# SCH_Lanchester-Mower_2024-05-06_1.net
KiCad netlist of a schematic drawn in EasyEDA
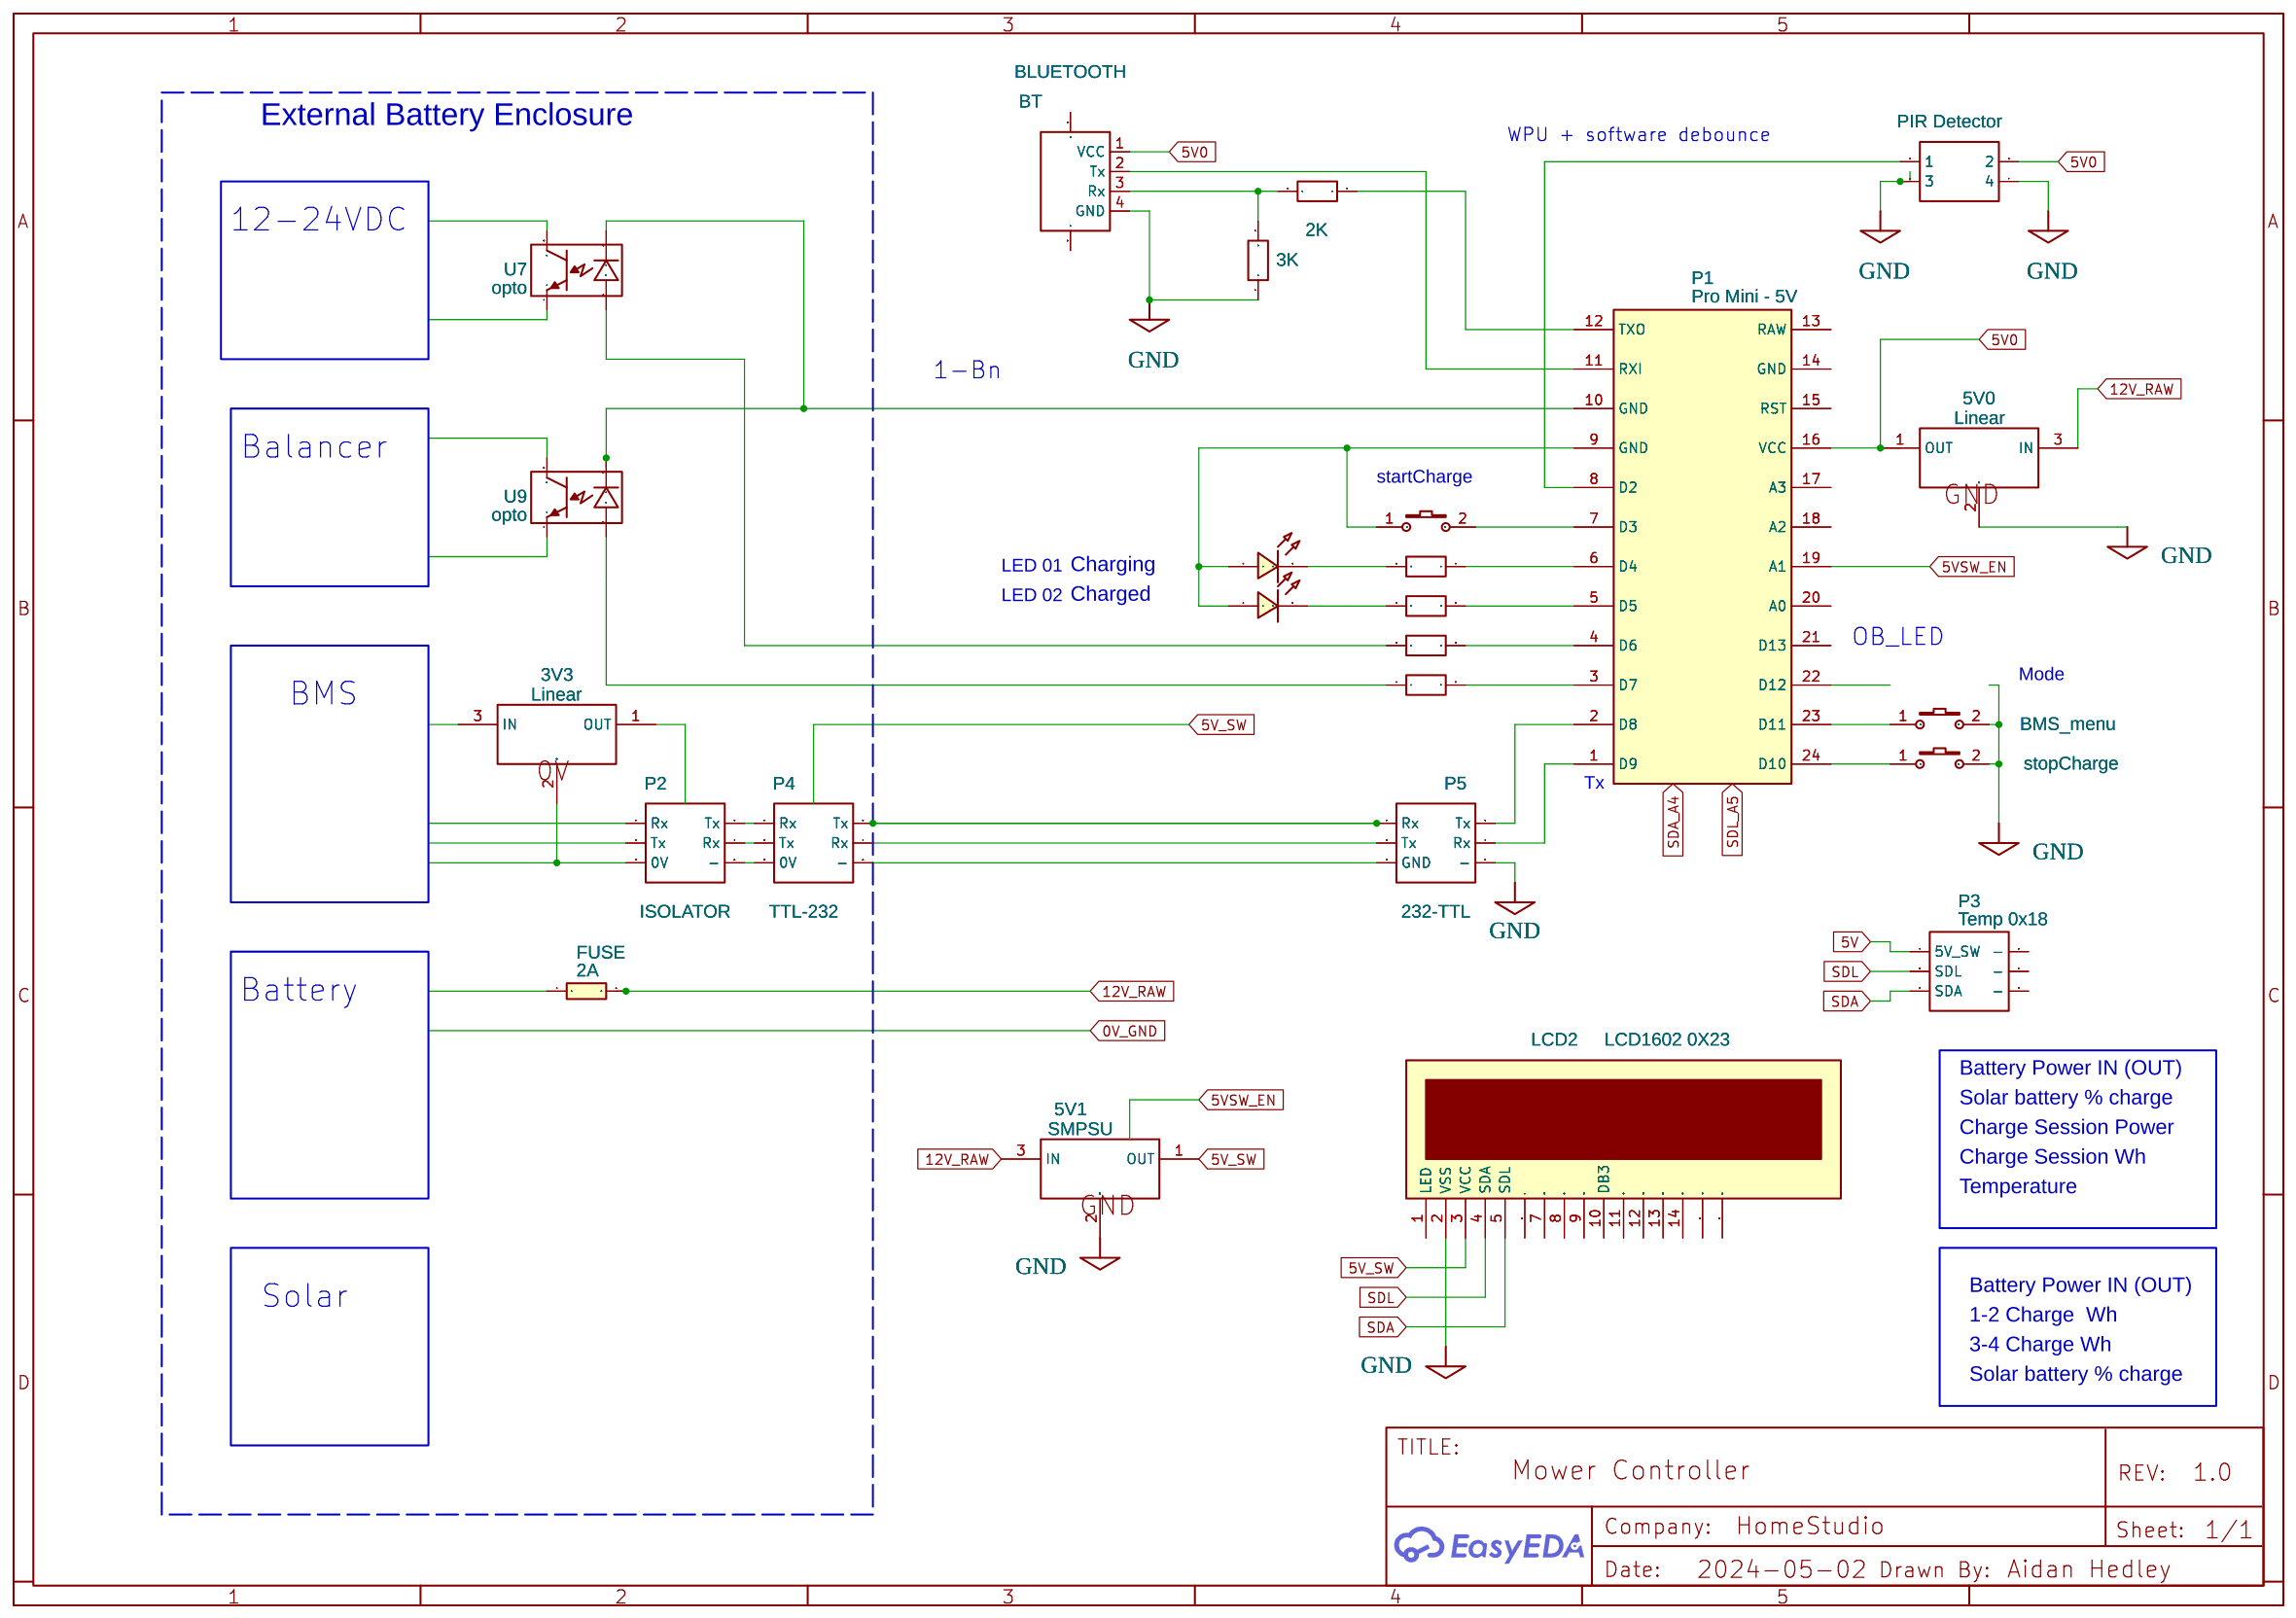
[diagram p0: schematic sheet]

(export (version "E")
  (design (tool "Eeschema 10.0.6"))
  (components
    (comp (ref "1R")
      (value "2K")
      (fields (field (name "Manufacturer Part") "贴片电阻ChipResistors"))
      (libsource (lib "") (part "贴片电阻CHIPRESISTORS_5"))
    )
    (comp (ref "3V3")
      (value "Linear")
      (fields (field (name "Manufacturer Part") "CJ78L05") (field (name "Manufacturer") "CJ"))
      (libsource (lib "") (part "7805(SOT-89)_2"))
    )
    (comp (ref "4R")
      (value "3K")
      (fields (field (name "Manufacturer Part") "贴片电阻ChipResistors"))
      (libsource (lib "") (part "贴片电阻CHIPRESISTORS_1"))
    )
    (comp (ref "5R")
      (value "R2")
      (fields (field (name "Manufacturer Part") "贴片电阻ChipResistors"))
      (libsource (lib "") (part "贴片电阻CHIPRESISTORS_4"))
    )
    (comp (ref "5V0")
      (value "Linear")
      (fields (field (name "Manufacturer Part") "CJ78L05") (field (name "Manufacturer") "CJ"))
      (libsource (lib "") (part "7805(SOT-89)_1"))
    )
    (comp (ref "5V1")
      (value "SMPSU")
      (fields (field (name "Manufacturer Part") "CJ78L05") (field (name "Manufacturer") "CJ"))
      (libsource (lib "") (part "7805(SOT-89)"))
    )
    (comp (ref "12R")
      (value "R2")
      (fields (field (name "Manufacturer Part") "贴片电阻ChipResistors"))
      (libsource (lib "") (part "贴片电阻CHIPRESISTORS_2"))
    )
    (comp (ref "14R")
      (value "R2")
      (fields (field (name "Manufacturer Part") "贴片电阻ChipResistors"))
      (libsource (lib "") (part "贴片电阻CHIPRESISTORS"))
    )
    (comp (ref "15R")
      (value "R2")
      (fields (field (name "Manufacturer Part") "贴片电阻ChipResistors"))
      (libsource (lib "") (part "贴片电阻CHIPRESISTORS_3"))
    )
    (comp (ref "BLUETOOTH")
      (value "BT")
      (fields (field (name "Manufacturer Part") "USB-05") (field (name "Manufacturer") "SOFNG"))
      (libsource (lib "") (part "USB-Type A_Male"))
    )
    (comp (ref "FUSE") (value "2A") (libsource (lib "") (part "L0603_EU")))
    (comp (ref "J2") (value "PIR Detector") (libsource (lib "") (part "HDR-M-2.54_2x2")))
    (comp (ref "KEY1")
      (value "stopCharge")
      (fields (field (name "Manufacturer Part") "K2-1107ST-A4SW-06"))
      (libsource (lib "") (part "K2-3.6×6.1_SMD"))
    )
    (comp (ref "KEY3")
      (value "BMS_menu")
      (fields (field (name "Manufacturer Part") "K2-1107ST-A4SW-06"))
      (libsource (lib "") (part "K2-3.6×6.1_SMD"))
    )
    (comp (ref "KEY4")
      (value "Start_Charge")
      (fields (field (name "Manufacturer Part") "K2-1107ST-A4SW-06"))
      (libsource (lib "") (part "K2-3.6×6.1_SMD"))
    )
    (comp (ref "LCD2")
      (value "LCD1602 0X23")
      (fields
        (field (name "Manufacturer Part") "LCM1602K-NSW-BBW")
        (field (name "Manufacturer") "LONTECH(厦门龙特)")
      )
      (libsource (lib "") (part "LCD1602"))
    )
    (comp (ref "LED1")
      (value "LED-0603_R")
      (fields
        (field (name "Manufacturer Part") "19-217/R6C-AL1M2VY/3T")
        (field (name "Manufacturer") "EVERLIGHT(台湾亿光)")
      )
      (libsource (lib "") (part "LED-0603_R"))
    )
    (comp (ref "LED3")
      (value "LED-0603_R")
      (fields
        (field (name "Manufacturer Part") "19-217/R6C-AL1M2VY/3T")
        (field (name "Manufacturer") "EVERLIGHT(台湾亿光)")
      )
      (libsource (lib "") (part "LED-0603_R"))
    )
    (comp (ref "P1") (value "Pro Mini - 5V") (libsource (lib "") (part "Pro Micro - 5V - large")))
    (comp (ref "P2")
      (value "ISOLATOR")
      (fields (field (name "Manufacturer Part") "2X3 2.54mm IDC Box") (field (name "Manufacturer") "BOOMELE"))
      (libsource (lib "") (part "HDR-IDC-2.54-2X3P_1"))
    )
    (comp (ref "P3")
      (value "Temp 0x18")
      (fields (field (name "Manufacturer Part") "2X3 2.54mm IDC Box") (field (name "Manufacturer") "BOOMELE"))
      (libsource (lib "") (part "HDR-IDC-2.54-2X3P"))
    )
    (comp (ref "P4")
      (value "TTL-232")
      (fields (field (name "Manufacturer Part") "2X3 2.54mm IDC Box") (field (name "Manufacturer") "BOOMELE"))
      (libsource (lib "") (part "HDR-IDC-2.54-2X3P_1"))
    )
    (comp (ref "P5")
      (value "232-TTL")
      (fields (field (name "Manufacturer Part") "2X3 2.54mm IDC Box") (field (name "Manufacturer") "BOOMELE"))
      (libsource (lib "") (part "HDR-IDC-2.54-2X3P_2"))
    )
    (comp (ref "U7")
      (value "opto")
      (fields (field (name "Manufacturer Part") "OPB841L55") (field (name "Manufacturer") "OPTEK"))
      (libsource (lib "") (part "OPB841L55"))
    )
    (comp (ref "U9")
      (value "opto")
      (fields (field (name "Manufacturer Part") "OPB841L55") (field (name "Manufacturer") "OPTEK"))
      (libsource (lib "") (part "OPB841L55"))
    )
  )
  (nets
    (net (code "2") (name "5V") (class "Default")
      (node (ref "P3") (pin "1") (pinfunction "5V_SW_1") (pintype "unspecified"))
    )
    (net (code "3") (name "5V0") (class "Default")
      (node (ref "5V0") (pin "1") (pinfunction "OUT_1") (pintype "passive"))
      (node (ref "BLUETOOTH") (pin "1") (pinfunction "VCC_1") (pintype "input"))
      (node (ref "J2") (pin "2") (pinfunction "2_2") (pintype "input"))
      (node (ref "P1") (pin "16") (pinfunction "VCC_16") (pintype "unspecified"))
    )
    (net (code "4") (name "5VSW_EN") (class "Default")
      (node (ref "P1") (pin "19") (pinfunction "A1_19") (pintype "unspecified"))
    )
    (net (code "5") (name "5V_SW") (class "Default")
      (node (ref "5V1") (pin "1") (pinfunction "OUT_1") (pintype "passive"))
      (node (ref "LCD2") (pin "3") (pinfunction "VCC_3") (pintype "unspecified"))
    )
    (net (code "6") (name "12V_RAW") (class "Default")
      (node (ref "5V0") (pin "3") (pinfunction "IN_3") (pintype "passive"))
      (node (ref "5V1") (pin "3") (pinfunction "IN_3") (pintype "passive"))
      (node (ref "FUSE") (pin "2") (pinfunction "2_2") (pintype "unspecified"))
    )
    (net (code "7") (name "GND") (class "Default")
      (node (ref "4R") (pin "1") (pinfunction "1_1") (pintype "unspecified"))
      (node (ref "5V0") (pin "2") (pinfunction "GND_2") (pintype "passive"))
      (node (ref "5V1") (pin "2") (pinfunction "GND_2") (pintype "passive"))
      (node (ref "BLUETOOTH") (pin "4") (pinfunction "GND_4") (pintype "input"))
      (node (ref "J2") (pin "3") (pinfunction "3_3") (pintype "input"))
      (node (ref "J2") (pin "4") (pinfunction "4_4") (pintype "input"))
      (node (ref "KEY1") (pin "2") (pinfunction "2_2") (pintype "unspecified"))
      (node (ref "KEY3") (pin "2") (pinfunction "2_2") (pintype "unspecified"))
      (node (ref "LCD2") (pin "2") (pinfunction "VSS_2") (pintype "unspecified"))
      (node (ref "P5") (pin "6") (pinfunction "-_6") (pintype "unspecified"))
    )
    (net (code "8") (name "Net-(3V3-GND)") (class "Default")
      (node (ref "3V3") (pin "2") (pinfunction "GND_2") (pintype "passive"))
      (node (ref "P2") (pin "5") (pinfunction "0V_5") (pintype "unspecified"))
    )
    (net (code "9") (name "Net-(5R-Pad2)") (class "Default")
      (node (ref "5R") (pin "2") (pinfunction "2_2") (pintype "unspecified"))
      (node (ref "LED3") (pin "2") (pinfunction "2_2") (pintype "unspecified"))
    )
    (net (code "10") (name "Net-(12R-Pad1)") (class "Default")
      (node (ref "12R") (pin "1") (pinfunction "1_1") (pintype "unspecified"))
      (node (ref "LED1") (pin "2") (pinfunction "2_2") (pintype "unspecified"))
    )
    (net (code "11") (name "Net-(14R-Pad1)") (class "Default")
      (node (ref "14R") (pin "1") (pinfunction "1_1") (pintype "unspecified"))
      (node (ref "U7") (pin "2") (pinfunction "2_2") (pintype "unspecified"))
    )
    (net (code "12") (name "Net-(15R-Pad1)") (class "Default")
      (node (ref "15R") (pin "1") (pinfunction "1_1") (pintype "unspecified"))
      (node (ref "U9") (pin "2") (pinfunction "2_2") (pintype "unspecified"))
    )
    (net (code "13") (name "Net-(BLUETOOTH-Rx)") (class "Default")
      (node (ref "1R") (pin "2") (pinfunction "2_2") (pintype "unspecified"))
      (node (ref "4R") (pin "2") (pinfunction "2_2") (pintype "unspecified"))
      (node (ref "BLUETOOTH") (pin "3") (pinfunction "Rx_3") (pintype "input"))
    )
    (net (code "14") (name "Net-(BLUETOOTH-Tx)") (class "Default")
      (node (ref "BLUETOOTH") (pin "2") (pinfunction "Tx_2") (pintype "input"))
      (node (ref "P1") (pin "11") (pinfunction "RXI_11") (pintype "unspecified"))
    )
    (net (code "15") (name "Net-(KEY4-Pad1)") (class "Default")
      (node (ref "KEY4") (pin "1") (pinfunction "1_1") (pintype "unspecified"))
      (node (ref "LED1") (pin "1") (pinfunction "1_1") (pintype "unspecified"))
      (node (ref "LED3") (pin "1") (pinfunction "1_1") (pintype "unspecified"))
      (node (ref "P1") (pin "9") (pinfunction "GND_9") (pintype "unspecified"))
    )
    (net (code "16") (name "Net-(P1-D2)") (class "Default")
      (node (ref "J2") (pin "1") (pinfunction "1_1") (pintype "input"))
      (node (ref "P1") (pin "8") (pinfunction "D2_8") (pintype "unspecified"))
    )
    (net (code "17") (name "Net-(P1-D3)") (class "Default")
      (node (ref "KEY4") (pin "2") (pinfunction "2_2") (pintype "unspecified"))
      (node (ref "P1") (pin "7") (pinfunction "D3_7") (pintype "unspecified"))
    )
    (net (code "18") (name "Net-(P1-D4)") (class "Default")
      (node (ref "5R") (pin "1") (pinfunction "1_1") (pintype "unspecified"))
      (node (ref "P1") (pin "6") (pinfunction "D4_6") (pintype "unspecified"))
    )
    (net (code "19") (name "Net-(P1-D5)") (class "Default")
      (node (ref "12R") (pin "2") (pinfunction "2_2") (pintype "unspecified"))
      (node (ref "P1") (pin "5") (pinfunction "D5_5") (pintype "unspecified"))
    )
    (net (code "20") (name "Net-(P1-D6)") (class "Default")
      (node (ref "14R") (pin "2") (pinfunction "2_2") (pintype "unspecified"))
      (node (ref "P1") (pin "4") (pinfunction "D6_4") (pintype "unspecified"))
    )
    (net (code "21") (name "Net-(P1-D7)") (class "Default")
      (node (ref "15R") (pin "2") (pinfunction "2_2") (pintype "unspecified"))
      (node (ref "P1") (pin "3") (pinfunction "D7_3") (pintype "unspecified"))
    )
    (net (code "22") (name "Net-(P1-D8)") (class "Default")
      (node (ref "P1") (pin "2") (pinfunction "D8_2") (pintype "unspecified"))
      (node (ref "P5") (pin "2") (pinfunction "Tx_2") (pintype "unspecified"))
    )
    (net (code "23") (name "Net-(P1-D9)") (class "Default")
      (node (ref "P1") (pin "1") (pinfunction "D9_1") (pintype "unspecified"))
      (node (ref "P5") (pin "4") (pinfunction "Rx_4") (pintype "unspecified"))
    )
    (net (code "24") (name "Net-(P1-D10)") (class "Default")
      (node (ref "KEY1") (pin "1") (pinfunction "1_1") (pintype "unspecified"))
      (node (ref "P1") (pin "24") (pinfunction "D10_24") (pintype "unspecified"))
    )
    (net (code "25") (name "Net-(P1-D11)") (class "Default")
      (node (ref "KEY3") (pin "1") (pinfunction "1_1") (pintype "unspecified"))
      (node (ref "P1") (pin "23") (pinfunction "D11_23") (pintype "unspecified"))
    )
    (net (code "26") (name "Net-(P1-GND-Pad10)") (class "Default")
      (node (ref "P1") (pin "10") (pinfunction "GND_10") (pintype "unspecified"))
      (node (ref "U7") (pin "1") (pinfunction "1_1") (pintype "unspecified"))
      (node (ref "U9") (pin "1") (pinfunction "1_1") (pintype "unspecified"))
    )
    (net (code "27") (name "Net-(P1-TXO)") (class "Default")
      (node (ref "1R") (pin "1") (pinfunction "1_1") (pintype "unspecified"))
      (node (ref "P1") (pin "12") (pinfunction "TXO_12") (pintype "unspecified"))
    )
    (net (code "28") (name "Net-(P2--)") (class "Default")
      (node (ref "P2") (pin "6") (pinfunction "-_6") (pintype "unspecified"))
      (node (ref "P4") (pin "5") (pinfunction "0V_5") (pintype "unspecified"))
    )
    (net (code "29") (name "Net-(P2-Rx-Pad4)") (class "Default")
      (node (ref "P2") (pin "4") (pinfunction "Rx_4") (pintype "unspecified"))
      (node (ref "P4") (pin "3") (pinfunction "Tx_3") (pintype "unspecified"))
    )
    (net (code "30") (name "Net-(P2-Tx-Pad2)") (class "Default")
      (node (ref "P2") (pin "2") (pinfunction "Tx_2") (pintype "unspecified"))
      (node (ref "P4") (pin "1") (pinfunction "Rx_1") (pintype "unspecified"))
    )
    (net (code "31") (name "Net-(P4--)") (class "Default")
      (node (ref "P4") (pin "6") (pinfunction "-_6") (pintype "unspecified"))
      (node (ref "P5") (pin "5") (pinfunction "GND_5") (pintype "unspecified"))
    )
    (net (code "32") (name "Net-(P4-Rx-Pad4)") (class "Default")
      (node (ref "P4") (pin "4") (pinfunction "Rx_4") (pintype "unspecified"))
      (node (ref "P5") (pin "3") (pinfunction "Tx_3") (pintype "unspecified"))
    )
    (net (code "33") (name "Net-(P4-Tx-Pad2)") (class "Default")
      (node (ref "P4") (pin "2") (pinfunction "Tx_2") (pintype "unspecified"))
      (node (ref "P5") (pin "1") (pinfunction "Rx_1") (pintype "unspecified"))
    )
    (net (code "34") (name "SDA") (class "Default")
      (node (ref "LCD2") (pin "5") (pinfunction "SDL_5") (pintype "unspecified"))
      (node (ref "P3") (pin "5") (pinfunction "SDA_5") (pintype "unspecified"))
    )
    (net (code "36") (name "SDL") (class "Default")
      (node (ref "LCD2") (pin "4") (pinfunction "SDA_4") (pintype "unspecified"))
      (node (ref "P3") (pin "3") (pinfunction "SDL_3") (pintype "unspecified"))
    )
    (net (code "38") (name "unconnected-(3V3-IN-Pad3)") (class "Default")
      (node (ref "3V3") (pin "3") (pinfunction "IN_3") (pintype "passive"))
    )
    (net (code "39") (name "unconnected-(3V3-OUT-Pad1)") (class "Default")
      (node (ref "3V3") (pin "1") (pinfunction "OUT_1") (pintype "passive"))
    )
    (net (code "40") (name "unconnected-(BLUETOOTH-Pad5)") (class "Default")
      (node (ref "BLUETOOTH") (pin "5") (pinfunction "5_5") (pintype "unspecified"))
    )
    (net (code "41") (name "unconnected-(BLUETOOTH-Pad6)") (class "Default")
      (node (ref "BLUETOOTH") (pin "6") (pinfunction "6_6") (pintype "unspecified"))
    )
    (net (code "42") (name "unconnected-(FUSE-Pad1)") (class "Default")
      (node (ref "FUSE") (pin "1") (pinfunction "1_1") (pintype "unspecified"))
    )
    (net (code "43") (name "unconnected-(LCD2-BLK-Pad16)") (class "Default")
      (node (ref "LCD2") (pin "16") (pinfunction "BLK_16") (pintype "unspecified"))
    )
    (net (code "44") (name "unconnected-(LCD2-DB0-Pad7)") (class "Default")
      (node (ref "LCD2") (pin "7") (pinfunction "DB0_7") (pintype "unspecified"))
    )
    (net (code "45") (name "unconnected-(LCD2-DB1-Pad8)") (class "Default")
      (node (ref "LCD2") (pin "8") (pinfunction "DB1_8") (pintype "unspecified"))
    )
    (net (code "46") (name "unconnected-(LCD2-DB2-Pad9)") (class "Default")
      (node (ref "LCD2") (pin "9") (pinfunction "DB2_9") (pintype "unspecified"))
    )
    (net (code "47") (name "unconnected-(LCD2-DB3-Pad10)") (class "Default")
      (node (ref "LCD2") (pin "10") (pinfunction "DB3_10") (pintype "unspecified"))
    )
    (net (code "48") (name "unconnected-(LCD2-DB4-Pad11)") (class "Default")
      (node (ref "LCD2") (pin "11") (pinfunction "DB4_11") (pintype "unspecified"))
    )
    (net (code "49") (name "unconnected-(LCD2-DB5-Pad12)") (class "Default")
      (node (ref "LCD2") (pin "12") (pinfunction "DB5_12") (pintype "unspecified"))
    )
    (net (code "50") (name "unconnected-(LCD2-DB6-Pad13)") (class "Default")
      (node (ref "LCD2") (pin "13") (pinfunction "DB6_13") (pintype "unspecified"))
    )
    (net (code "51") (name "unconnected-(LCD2-DB7-Pad14)") (class "Default")
      (node (ref "LCD2") (pin "14") (pinfunction "DB7_14") (pintype "unspecified"))
    )
    (net (code "52") (name "unconnected-(LCD2-E-Pad6)") (class "Default")
      (node (ref "LCD2") (pin "6") (pinfunction "E_6") (pintype "unspecified"))
    )
    (net (code "53") (name "unconnected-(LCD2-LED-Pad1)") (class "Default")
      (node (ref "LCD2") (pin "1") (pinfunction "LED_1") (pintype "unspecified"))
    )
    (net (code "54") (name "unconnected-(LCD2-LED-Pad15)") (class "Default")
      (node (ref "LCD2") (pin "15") (pinfunction "LED_15") (pintype "unspecified"))
    )
    (net (code "55") (name "unconnected-(P1-A0-Pad20)") (class "Default")
      (node (ref "P1") (pin "20") (pinfunction "A0_20") (pintype "unspecified"))
    )
    (net (code "56") (name "unconnected-(P1-A2-Pad18)") (class "Default")
      (node (ref "P1") (pin "18") (pinfunction "A2_18") (pintype "unspecified"))
    )
    (net (code "57") (name "unconnected-(P1-A3-Pad17)") (class "Default")
      (node (ref "P1") (pin "17") (pinfunction "A3_17") (pintype "unspecified"))
    )
    (net (code "58") (name "unconnected-(P1-D12-Pad22)") (class "Default")
      (node (ref "P1") (pin "22") (pinfunction "D12_22") (pintype "unspecified"))
    )
    (net (code "59") (name "unconnected-(P1-D13-Pad21)") (class "Default")
      (node (ref "P1") (pin "21") (pinfunction "D13_21") (pintype "unspecified"))
    )
    (net (code "60") (name "unconnected-(P1-GND-Pad14)") (class "Default")
      (node (ref "P1") (pin "14") (pinfunction "GND_14") (pintype "unspecified"))
    )
    (net (code "61") (name "unconnected-(P1-RAW-Pad13)") (class "Default")
      (node (ref "P1") (pin "13") (pinfunction "RAW_13") (pintype "unspecified"))
    )
    (net (code "62") (name "unconnected-(P1-RST-Pad15)") (class "Default")
      (node (ref "P1") (pin "15") (pinfunction "RST_15") (pintype "unspecified"))
    )
    (net (code "63") (name "unconnected-(P2-Rx-Pad1)") (class "Default")
      (node (ref "P2") (pin "1") (pinfunction "Rx_1") (pintype "unspecified"))
    )
    (net (code "64") (name "unconnected-(P2-Tx-Pad3)") (class "Default")
      (node (ref "P2") (pin "3") (pinfunction "Tx_3") (pintype "unspecified"))
    )
    (net (code "65") (name "unconnected-(P3---Pad2)") (class "Default")
      (node (ref "P3") (pin "2") (pinfunction "-_2") (pintype "unspecified"))
    )
    (net (code "66") (name "unconnected-(P3---Pad4)") (class "Default")
      (node (ref "P3") (pin "4") (pinfunction "-_4") (pintype "unspecified"))
    )
    (net (code "67") (name "unconnected-(P3---Pad6)") (class "Default")
      (node (ref "P3") (pin "6") (pinfunction "-_6") (pintype "unspecified"))
    )
    (net (code "68") (name "unconnected-(U7-Pad3)") (class "Default")
      (node (ref "U7") (pin "3") (pinfunction "3_3") (pintype "unspecified"))
    )
    (net (code "69") (name "unconnected-(U7-Pad4)") (class "Default")
      (node (ref "U7") (pin "4") (pinfunction "4_4") (pintype "unspecified"))
    )
    (net (code "70") (name "unconnected-(U9-Pad3)") (class "Default")
      (node (ref "U9") (pin "3") (pinfunction "3_3") (pintype "unspecified"))
    )
    (net (code "71") (name "unconnected-(U9-Pad4)") (class "Default")
      (node (ref "U9") (pin "4") (pinfunction "4_4") (pintype "unspecified"))
    )
  )
)
